# WX0_010_828DL.net
KiCad netlist of a schematic drawn in Altium Designer
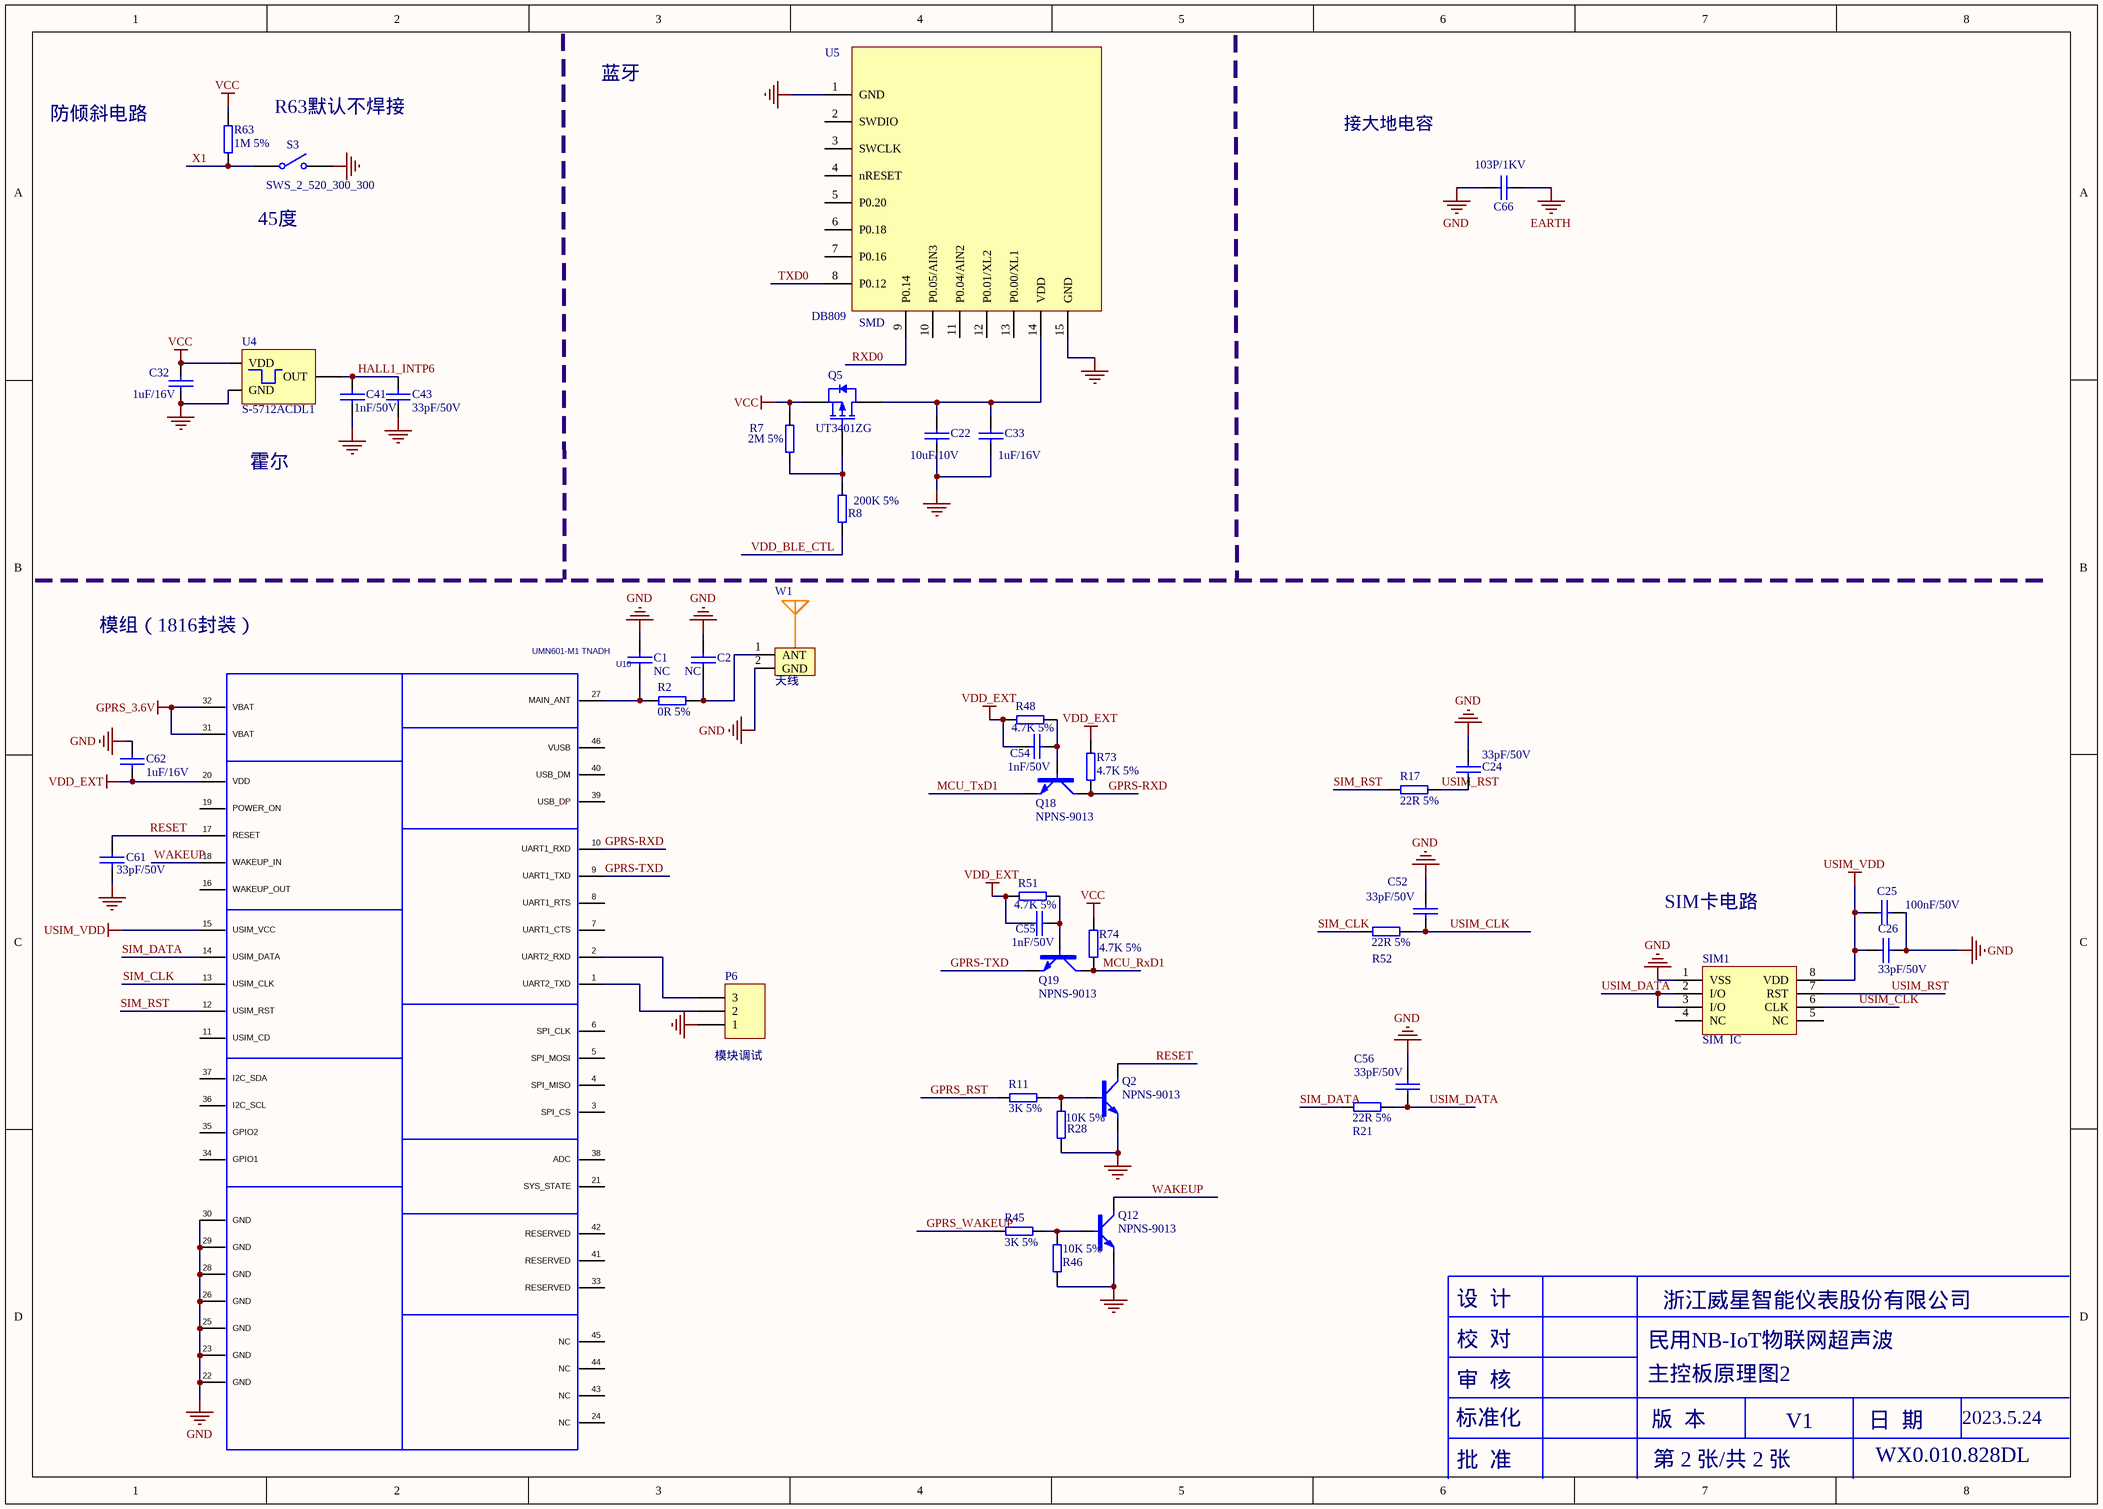
[diagram p0: WX0.010.828DL.SchDoc]

(export (version "E")
  (design (tool "Eeschema 10.0.6"))
  (components
    (comp (ref "C1")
      (value "NC")
      (footprint "CAP0603")
      (libsource (lib "Database_Libs2") (part "CC03JPO9_12P"))
    )
    (comp (ref "C2")
      (value "NC")
      (footprint "CAP0603")
      (libsource (lib "Database_Libs2") (part "CC03JPO9_12P"))
    )
    (comp (ref "C22")
      (value "10uF/10V")
      (footprint "CAP0603")
      (description "106pF,10 V,±10%,0603,村田,GRM188R61A106KE47D")
      (fields (field (name "PART NUMBER") "101020103-0026"))
      (libsource (lib "Database_Libs2") (part "CC03K5R6_10U"))
    )
    (comp (ref "C24")
      (value "33pF/50V")
      (footprint "CAP0603")
      (description "33pF,50 V,±10%,0603,国巨,CC0603KRNPO9BN33")
      (fields (field (name "PART NUMBER") "101020103-0027"))
      (libsource (lib "Database_Libs2") (part "CC03KPO9_33P"))
    )
    (comp (ref "C25")
      (value "100nF/50V")
      (footprint "CAP0603")
      (description "104pF,50 V,±10%,0603,国巨,CC0603KRX7R9BB104")
      (fields (field (name "PART NUMBER") "101020103-0021"))
      (libsource (lib "Database_Libs2") (part "CC03K7R9_100N"))
    )
    (comp (ref "C26")
      (value "33pF/50V")
      (footprint "CAP0603")
      (description "33pF,50 V,±10%,0603,国巨,CC0603KRNPO9BN33")
      (fields (field (name "PART NUMBER") "101020103-0027"))
      (libsource (lib "Database_Libs2") (part "CC03KPO9_33P"))
    )
    (comp (ref "C32")
      (value "1uF/16V")
      (footprint "CAP0603")
      (description "105pF,16 V,±10%,0603,国巨,CC0603KRX7R7BB105")
      (fields (field (name "PART NUMBER") "101020103-0003"))
      (libsource (lib "Database_Libs2") (part "CC03K7R7_1U"))
    )
    (comp (ref "C33")
      (value "1uF/16V")
      (footprint "CAP0603")
      (description "105pF,16 V,±10%,0603,国巨,CC0603KRX7R7BB105")
      (fields (field (name "PART NUMBER") "101020103-0003"))
      (libsource (lib "Database_Libs2") (part "CC03K7R7_1U"))
    )
    (comp (ref "C41")
      (value "1nF/50V")
      (footprint "CAP0603")
      (description "102pF,50 V,±10%,0603,国巨,CC0603KRX7R9BB102")
      (fields (field (name "PART NUMBER") "101020103-0022"))
      (libsource (lib "Database_Libs2") (part "CC03K7R9_1N"))
    )
    (comp (ref "C43")
      (value "33pF/50V")
      (footprint "CAP0603")
      (description "33pF,50 V,±10%,0603,国巨,CC0603KRNPO9BN33")
      (fields (field (name "PART NUMBER") "101020103-0027"))
      (libsource (lib "Database_Libs2") (part "CC03KPO9_33P"))
    )
    (comp (ref "C52")
      (value "33pF/50V")
      (footprint "CAP0603")
      (description "33pF,50 V,±10%,0603,国巨,CC0603KRNPO9BN33")
      (fields (field (name "PART NUMBER") "101020103-0027"))
      (libsource (lib "Database_Libs2") (part "CC03KPO9_33P"))
    )
    (comp (ref "C54")
      (value "1nF/50V")
      (footprint "CAP0603")
      (description "102pF,50 V,±10%,0603,国巨,CC0603KRX7R9BB102")
      (fields (field (name "PART NUMBER") "101020103-0022"))
      (libsource (lib "Database_Libs1") (part "CC03K7R9_1N"))
    )
    (comp (ref "C55")
      (value "1nF/50V")
      (footprint "CAP0603")
      (description "102pF,50 V,±10%,0603,国巨,CC0603KRX7R9BB102")
      (fields (field (name "PART NUMBER") "101020103-0022"))
      (libsource (lib "Database_Libs1") (part "CC03K7R9_1N"))
    )
    (comp (ref "C56")
      (value "33pF/50V")
      (footprint "CAP0603")
      (description "33pF,50 V,±10%,0603,国巨,CC0603KRNPO9BN33")
      (fields (field (name "PART NUMBER") "101020103-0027"))
      (libsource (lib "Database_Libs2") (part "CC03KPO9_33P"))
    )
    (comp (ref "C61")
      (value "33pF/50V")
      (footprint "CAP0603")
      (description "33pF,50 V,±10%,0603,国巨,CC0603KRNPO9BN33")
      (fields (field (name "PART NUMBER") "101020103-0027"))
      (libsource (lib "Database_Libs2") (part "CC03KPO9_33P"))
    )
    (comp (ref "C62")
      (value "1uF/16V")
      (footprint "CAP0603")
      (description "105pF,16 V,±10%,0603,国巨,CC0603KRX7R7BB105")
      (fields (field (name "PART NUMBER") "101020103-0003"))
      (libsource (lib "Database_Libs1") (part "CC03K7R7_1U"))
    )
    (comp (ref "C66")
      (value "103P/1KV")
      (footprint "CAP1206")
      (description "103P/1KV,±10％,1206")
      (fields (field (name "PART NUMBER") "101020101-0003"))
      (libsource (lib "altium-import") (part "root_3_CC03K7R9_100N_"))
    )
    (comp (ref "P6")
      (value "模块调试")
      (footprint "PIN254_1*3*WXHJ")
      (description "1*3 ，Φ1.0 ，2.54mm，直脚,无需焊接器件")
      (fields (field (name "PART NUMBER") "AD_WXHJ_PinHeader_04"))
      (libsource (lib "Database_Libs2") (part "PIN254_1*3*WXHJ"))
    )
    (comp (ref "Q2")
      (value "NPNS-9013")
      (footprint "SOT-23")
      (description "9013,NPN,SOT-23,长电,S9013")
      (fields (field (name "PART NUMBER") "101040201-0002"))
      (libsource (lib "Database_Libs2") (part "03_NPNS-9013"))
    )
    (comp (ref "Q5")
      (value "UT3401ZG")
      (footprint "SOT-23")
      (description "UT3401ZG,P-MOS,SOT-23,UTC,UT3401ZG")
      (fields (field (name "PART NUMBER") "101040201-0013"))
      (libsource (lib "Database_Libs2") (part "03_P-UT3401ZG"))
    )
    (comp (ref "Q12")
      (value "NPNS-9013")
      (footprint "SOT-23")
      (description "9013,NPN,SOT-23,长电,S9013")
      (fields (field (name "PART NUMBER") "101040201-0002"))
      (libsource (lib "Database_Libs2") (part "03_NPNS-9013"))
    )
    (comp (ref "Q18")
      (value "NPNS-9013")
      (footprint "SOT-23")
      (description "9013,NPN,SOT-23,长电,S9013")
      (fields (field (name "PART NUMBER") "101040201-0002"))
      (libsource (lib "Database_Libs1") (part "03_NPNS-9013"))
    )
    (comp (ref "Q19")
      (value "NPNS-9013")
      (footprint "SOT-23")
      (description "9013,NPN,SOT-23,长电,S9013")
      (fields (field (name "PART NUMBER") "101040201-0002"))
      (libsource (lib "Database_Libs1") (part "03_NPNS-9013"))
    )
    (comp (ref "R2")
      (value "0R 5%")
      (footprint "RES0603")
      (description "国巨,±5%,0603,,155 ℃,-55 ℃,RC0603J2-070RL,无铅,200 ppm/℃,1/10W,,0R")
      (fields (field (name "PART NUMBER") "101010103-0001"))
      (libsource (lib "Database_Libs2") (part "RC03J_0R"))
    )
    (comp (ref "R7")
      (value "2M 5%")
      (footprint "RES0603")
      (description "国巨,±5%,0603,,155 ℃,-55 ℃,RC0603JR-072ML,含铅,100 ppm/℃,1/10W,,2M")
      (fields (field (name "PART NUMBER") "101010103-0025"))
      (libsource (lib "Database_Libs2") (part "RC03J_2M"))
    )
    (comp (ref "R8")
      (value "200K 5%")
      (footprint "RES0603")
      (description "200K,±5%,1/10W,0603,国巨,RC0603JR-07200KL")
      (fields (field (name "PART NUMBER") "101010103-0034"))
      (libsource (lib "Database_Libs2") (part "RC03J_200K"))
    )
    (comp (ref "R11")
      (value "3K 5%")
      (footprint "RES0603")
      (description "国巨,±5%,0603,,155 ℃,-55 ℃,RC0603JR-073KL,无铅,100 ppm/℃,1/10W,,3K")
      (fields (field (name "PART NUMBER") "101010103-0006"))
      (libsource (lib "Database_Libs2") (part "RC03J_3K"))
    )
    (comp (ref "R17")
      (value "22R 5%")
      (footprint "RES0603")
      (description "国巨,±5%,0603,,155 ℃,-55 ℃,RC0603JR-0722RL,无铅,200 ppm/℃,1/10W,,22欧")
      (fields (field (name "PART NUMBER") "101010103-0009"))
      (libsource (lib "Database_Libs2") (part "RC03J_22R"))
    )
    (comp (ref "R21")
      (value "22R 5%")
      (footprint "RES0603")
      (description "国巨,±5%,0603,,155 ℃,-55 ℃,RC0603JR-0722RL,无铅,200 ppm/℃,1/10W,,22欧")
      (fields (field (name "PART NUMBER") "101010103-0009"))
      (libsource (lib "Database_Libs2") (part "RC03J_22R"))
    )
    (comp (ref "R28")
      (value "10K 5%")
      (footprint "RES0603")
      (description "国巨,±5%,0603,,155 ℃,-55 ℃,RC0603JR-0710KL,无铅,200 ppm/℃,1/10W,,10K")
      (fields (field (name "PART NUMBER") "101010103-0003"))
      (libsource (lib "Database_Libs2") (part "RC03J_10K"))
    )
    (comp (ref "R45")
      (value "3K 5%")
      (footprint "RES0603")
      (description "国巨,±5%,0603,,155 ℃,-55 ℃,RC0603JR-073KL,无铅,100 ppm/℃,1/10W,,3K")
      (fields (field (name "PART NUMBER") "101010103-0006"))
      (libsource (lib "Database_Libs2") (part "RC03J_3K"))
    )
    (comp (ref "R46")
      (value "10K 5%")
      (footprint "RES0603")
      (description "国巨,±5%,0603,,155 ℃,-55 ℃,RC0603JR-0710KL,无铅,200 ppm/℃,1/10W,,10K")
      (fields (field (name "PART NUMBER") "101010103-0003"))
      (libsource (lib "Database_Libs2") (part "RC03J_10K"))
    )
    (comp (ref "R48")
      (value "4.7K 5%")
      (footprint "RES0603")
      (description "4.7K±5%,1/10W,0603")
      (fields (field (name "PART NUMBER") "101010103-0042"))
      (libsource (lib "Database_Libs2") (part "RC03J_4.7K"))
    )
    (comp (ref "R51")
      (value "4.7K 5%")
      (footprint "RES0603")
      (description "4.7K±5%,1/10W,0603")
      (fields (field (name "PART NUMBER") "101010103-0042"))
      (libsource (lib "Database_Libs2") (part "RC03J_4.7K"))
    )
    (comp (ref "R52")
      (value "22R 5%")
      (footprint "RES0603")
      (description "国巨,±5%,0603,,155 ℃,-55 ℃,RC0603JR-0722RL,无铅,200 ppm/℃,1/10W,,22欧")
      (fields (field (name "PART NUMBER") "101010103-0009"))
      (libsource (lib "Database_Libs2") (part "RC03J_22R"))
    )
    (comp (ref "R63")
      (value "1M 5%")
      (footprint "RES0603")
      (description "国巨,±5%,0603,,155 ℃,-55 ℃,RC0603JR-071ML,无铅,200 ppm/℃,1/10W,,1M")
      (fields (field (name "PART NUMBER") "101010103-0002"))
      (libsource (lib "Database_Libs2") (part "RC03J_1M"))
    )
    (comp (ref "R73")
      (value "4.7K 5%")
      (footprint "RES0603")
      (description "4.7K±5%,1/10W,0603")
      (fields (field (name "PART NUMBER") "101010103-0042"))
      (libsource (lib "Database_Libs2") (part "RC03J_4.7K"))
    )
    (comp (ref "R74")
      (value "4.7K 5%")
      (footprint "RES0603")
      (description "4.7K±5%,1/10W,0603")
      (fields (field (name "PART NUMBER") "101010103-0042"))
      (libsource (lib "Database_Libs2") (part "RC03J_4.7K"))
    )
    (comp (ref "S3")
      (value "SWS_2_520_300_300")
      (footprint "SWS_2_520_300")
      (description "CSX-SEN-645B,垂直45°开关转换,3*5.2mm,360°任意方位倾斜检测,深圳市成晟科技有限公司")
      (fields (field (name "PART NUMBER") "1011001-0051"))
      (libsource (lib "Database_Libs2") (part "07_SWS_2_520_300_300"))
    )
    (comp (ref "SIM1")
      (value "SIM  IC")
      (footprint "SIMIC")
      (libsource (lib "PCB_Project") (part "SIMCARD_1"))
    )
    (comp (ref "U4")
      (value "S-5712ACDL1")
      (footprint "SOT-23")
      (description "S-5712ACDL1,SOT23-3,3.5 V,1.6 V,2 uA,精工电子,S-5712ACDL1")
      (fields (field (name "PART NUMBER") "1010504-0002"))
      (libsource (lib "Database_Libs2") (part "01_S-5712ACDL1"))
    )
    (comp (ref "U5")
      (value "DB809")
      (footprint "DB809")
      (description "北高智蓝牙模块DB809")
      (fields (field (name "PART NUMBER") "1011402-0194") (field (name "SMD/DIP") "SMD"))
      (libsource (lib "Database_Libs2") (part "01_DB809"))
    )
    (comp (ref "U10")
      (value "UMN601-M1 TNADH")
      (footprint "N700-FIXTURE_DL_CFT_CQA")
      (description "N700-58-01,N700-58-01,通信模块,18.0mm*16.0mm*2.1mm,Band 5:850MHz/Band 8:900MHz,深圳市广和通无线股份有限公司")
      (fields (field (name "PART NUMBER") "1011402-0183"))
      (libsource (lib "Database_Libs2") (part "01_N700_CON_46"))
    )
    (comp (ref "W1")
      (value "天线")
      (footprint "ANT-tanpian")
      (description "UB06000058A,3*3.1*1.25mm,公头,单排,IPEX一代板端")
      (fields (field (name "PART NUMBER") "1010902-0145"))
      (libsource (lib "Database_Libs2") (part "天线"))
    )
  )
  (nets
    (net (code "1") (name "/GPRS-RXD") (class "Default")
      (node (ref "Q18") (pin "3") (pinfunction "C_3") (pintype "passive"))
      (node (ref "R73") (pin "1") (pinfunction "1_1") (pintype "passive"))
      (node (ref "U10") (pin "10") (pinfunction "UART1_RXD_10") (pintype "passive"))
    )
    (net (code "2") (name "/GPRS-TXD") (class "Default")
      (node (ref "Q19") (pin "2") (pinfunction "E_2") (pintype "passive"))
      (node (ref "U10") (pin "9") (pinfunction "UART1_TXD_9") (pintype "passive"))
    )
    (net (code "3") (name "/GPRS_RST") (class "Default")
      (node (ref "R11") (pin "1") (pinfunction "1_1") (pintype "passive"))
    )
    (net (code "4") (name "/GPRS_WAKEUP") (class "Default")
      (node (ref "R45") (pin "1") (pinfunction "1_1") (pintype "passive"))
    )
    (net (code "5") (name "/HALL1_INTP6") (class "Default")
      (node (ref "C41") (pin "1") (pinfunction "1_1") (pintype "passive"))
      (node (ref "C43") (pin "1") (pinfunction "1_1") (pintype "passive"))
      (node (ref "U4") (pin "2") (pinfunction "OUT_2") (pintype "passive"))
    )
    (net (code "6") (name "/MCU_RxD1") (class "Default")
      (node (ref "Q19") (pin "3") (pinfunction "C_3") (pintype "passive"))
      (node (ref "R74") (pin "1") (pinfunction "1_1") (pintype "passive"))
    )
    (net (code "7") (name "/MCU_TxD1") (class "Default")
      (node (ref "Q18") (pin "2") (pinfunction "E_2") (pintype "passive"))
    )
    (net (code "8") (name "/RESET") (class "Default")
      (node (ref "C61") (pin "2") (pinfunction "2_2") (pintype "passive"))
      (node (ref "Q2") (pin "3") (pinfunction "C_3") (pintype "passive"))
      (node (ref "U10") (pin "17") (pinfunction "RESET_17") (pintype "passive"))
    )
    (net (code "9") (name "/RXD0") (class "Default")
      (node (ref "U5") (pin "9") (pinfunction "P0.14_9") (pintype "passive"))
    )
    (net (code "10") (name "/SIM_CLK") (class "Default")
      (node (ref "R52") (pin "1") (pinfunction "1_1") (pintype "passive"))
      (node (ref "U10") (pin "13") (pinfunction "USIM_CLK_13") (pintype "passive"))
    )
    (net (code "11") (name "/SIM_DATA") (class "Default")
      (node (ref "R21") (pin "1") (pinfunction "1_1") (pintype "passive"))
      (node (ref "U10") (pin "14") (pinfunction "USIM_DATA_14") (pintype "passive"))
    )
    (net (code "12") (name "/SIM_RST") (class "Default")
      (node (ref "R17") (pin "1") (pinfunction "1_1") (pintype "passive"))
      (node (ref "U10") (pin "12") (pinfunction "USIM_RST_12") (pintype "passive"))
    )
    (net (code "13") (name "/TXD0") (class "Default")
      (node (ref "U5") (pin "8") (pinfunction "P0.12_8") (pintype "passive"))
    )
    (net (code "14") (name "/USIM_CLK") (class "Default")
      (node (ref "C52") (pin "1") (pinfunction "1_1") (pintype "passive"))
      (node (ref "R52") (pin "2") (pinfunction "2_2") (pintype "passive"))
      (node (ref "SIM1") (pin "6") (pinfunction "CLK_6") (pintype "passive"))
    )
    (net (code "15") (name "/USIM_DATA") (class "Default")
      (node (ref "C56") (pin "1") (pinfunction "1_1") (pintype "passive"))
      (node (ref "R21") (pin "2") (pinfunction "2_2") (pintype "passive"))
      (node (ref "SIM1") (pin "2") (pinfunction "I/O_2") (pintype "passive"))
      (node (ref "SIM1") (pin "3") (pinfunction "I/O_3") (pintype "passive"))
    )
    (net (code "16") (name "/USIM_RST") (class "Default")
      (node (ref "C24") (pin "1") (pinfunction "1_1") (pintype "passive"))
      (node (ref "R17") (pin "2") (pinfunction "2_2") (pintype "passive"))
      (node (ref "SIM1") (pin "7") (pinfunction "RST_7") (pintype "passive"))
    )
    (net (code "17") (name "/VDD_BLE_CTL") (class "Default")
      (node (ref "R8") (pin "1") (pinfunction "1_1") (pintype "passive"))
    )
    (net (code "18") (name "/WAKEUP") (class "Default")
      (node (ref "Q12") (pin "3") (pinfunction "C_3") (pintype "passive"))
      (node (ref "U10") (pin "18") (pinfunction "WAKEUP_IN_18") (pintype "passive"))
    )
    (net (code "19") (name "/X1") (class "Default")
      (node (ref "R63") (pin "1") (pinfunction "1_1") (pintype "passive"))
      (node (ref "S3") (pin "1") (pintype "passive"))
    )
    (net (code "20") (name "EARTH") (class "Default")
      (node (ref "C66") (pin "1") (pinfunction "1_1") (pintype "passive"))
    )
    (net (code "21") (name "GND") (class "Default")
      (node (ref "C1") (pin "2") (pinfunction "2_2") (pintype "passive"))
      (node (ref "C2") (pin "2") (pinfunction "2_2") (pintype "passive"))
      (node (ref "C22") (pin "2") (pinfunction "2_2") (pintype "passive"))
      (node (ref "C24") (pin "2") (pinfunction "2_2") (pintype "passive"))
      (node (ref "C25") (pin "1") (pinfunction "1_1") (pintype "passive"))
      (node (ref "C26") (pin "2") (pinfunction "2_2") (pintype "passive"))
      (node (ref "C32") (pin "2") (pinfunction "2_2") (pintype "passive"))
      (node (ref "C33") (pin "2") (pinfunction "2_2") (pintype "passive"))
      (node (ref "C41") (pin "2") (pinfunction "2_2") (pintype "passive"))
      (node (ref "C43") (pin "2") (pinfunction "2_2") (pintype "passive"))
      (node (ref "C52") (pin "2") (pinfunction "2_2") (pintype "passive"))
      (node (ref "C56") (pin "2") (pinfunction "2_2") (pintype "passive"))
      (node (ref "C61") (pin "1") (pinfunction "1_1") (pintype "passive"))
      (node (ref "C62") (pin "2") (pinfunction "2_2") (pintype "passive"))
      (node (ref "C66") (pin "2") (pinfunction "2_2") (pintype "passive"))
      (node (ref "P6") (pin "1") (pinfunction "1_1") (pintype "passive"))
      (node (ref "Q12") (pin "2") (pinfunction "E_2") (pintype "passive"))
      (node (ref "Q2") (pin "2") (pinfunction "E_2") (pintype "passive"))
      (node (ref "R28") (pin "1") (pinfunction "1_1") (pintype "passive"))
      (node (ref "R46") (pin "1") (pinfunction "1_1") (pintype "passive"))
      (node (ref "S3") (pin "2") (pintype "passive"))
      (node (ref "SIM1") (pin "1") (pinfunction "VSS_1") (pintype "passive"))
      (node (ref "U10") (pin "22") (pinfunction "GND_22") (pintype "passive"))
      (node (ref "U10") (pin "23") (pinfunction "GND_23") (pintype "passive"))
      (node (ref "U10") (pin "25") (pinfunction "GND_25") (pintype "passive"))
      (node (ref "U10") (pin "26") (pinfunction "GND_26") (pintype "passive"))
      (node (ref "U10") (pin "28") (pinfunction "GND_28") (pintype "passive"))
      (node (ref "U10") (pin "29") (pinfunction "GND_29") (pintype "passive"))
      (node (ref "U10") (pin "30") (pinfunction "GND_30") (pintype "passive"))
      (node (ref "U4") (pin "3") (pinfunction "GND_3") (pintype "passive"))
      (node (ref "U5") (pin "1") (pinfunction "GND_1") (pintype "passive"))
      (node (ref "U5") (pin "15") (pinfunction "GND_15") (pintype "passive"))
      (node (ref "W1") (pin "2") (pinfunction "GND_2") (pintype "passive"))
    )
    (net (code "22") (name "GPRS_3.6V") (class "Default")
      (node (ref "U10") (pin "31") (pinfunction "VBAT_31") (pintype "passive"))
      (node (ref "U10") (pin "32") (pinfunction "VBAT_32") (pintype "passive"))
    )
    (net (code "23") (name "Net-(Q2-B)") (class "Default")
      (node (ref "Q2") (pin "1") (pinfunction "B_1") (pintype "passive"))
      (node (ref "R11") (pin "2") (pinfunction "2_2") (pintype "passive"))
      (node (ref "R28") (pin "2") (pinfunction "2_2") (pintype "passive"))
    )
    (net (code "24") (name "Net-(Q5-D)") (class "Default")
      (node (ref "C22") (pin "1") (pinfunction "1_1") (pintype "passive"))
      (node (ref "C33") (pin "1") (pinfunction "1_1") (pintype "passive"))
      (node (ref "Q5") (pin "3") (pinfunction "D_3") (pintype "passive"))
      (node (ref "U5") (pin "14") (pinfunction "VDD_14") (pintype "passive"))
    )
    (net (code "25") (name "Net-(Q5-G)") (class "Default")
      (node (ref "Q5") (pin "1") (pinfunction "G_1") (pintype "passive"))
      (node (ref "R7") (pin "1") (pinfunction "1_1") (pintype "passive"))
      (node (ref "R8") (pin "2") (pinfunction "2_2") (pintype "passive"))
    )
    (net (code "26") (name "Net-(Q12-B)") (class "Default")
      (node (ref "Q12") (pin "1") (pinfunction "B_1") (pintype "passive"))
      (node (ref "R45") (pin "2") (pinfunction "2_2") (pintype "passive"))
      (node (ref "R46") (pin "2") (pinfunction "2_2") (pintype "passive"))
    )
    (net (code "27") (name "Net-(Q18-B)") (class "Default")
      (node (ref "C54") (pin "2") (pinfunction "2_2") (pintype "passive"))
      (node (ref "Q18") (pin "1") (pinfunction "B_1") (pintype "passive"))
      (node (ref "R48") (pin "1") (pinfunction "1_1") (pintype "passive"))
    )
    (net (code "28") (name "Net-(Q19-B)") (class "Default")
      (node (ref "C55") (pin "2") (pinfunction "2_2") (pintype "passive"))
      (node (ref "Q19") (pin "1") (pinfunction "B_1") (pintype "passive"))
      (node (ref "R51") (pin "1") (pinfunction "1_1") (pintype "passive"))
    )
    (net (code "29") (name "Net-(U10-MAIN_ANT)") (class "Default")
      (node (ref "C1") (pin "1") (pinfunction "1_1") (pintype "passive"))
      (node (ref "R2") (pin "2") (pinfunction "2_2") (pintype "passive"))
      (node (ref "U10") (pin "27") (pinfunction "MAIN_ANT_27") (pintype "passive"))
    )
    (net (code "30") (name "Net-(U10-UART2_RXD)") (class "Default")
      (node (ref "P6") (pin "3") (pinfunction "3_3") (pintype "passive"))
      (node (ref "U10") (pin "2") (pinfunction "UART2_RXD_2") (pintype "passive"))
    )
    (net (code "31") (name "Net-(U10-UART2_TXD)") (class "Default")
      (node (ref "P6") (pin "2") (pinfunction "2_2") (pintype "passive"))
      (node (ref "U10") (pin "1") (pinfunction "UART2_TXD_1") (pintype "passive"))
    )
    (net (code "32") (name "Net-(W1-ANT)") (class "Default")
      (node (ref "C2") (pin "1") (pinfunction "1_1") (pintype "passive"))
      (node (ref "R2") (pin "1") (pinfunction "1_1") (pintype "passive"))
      (node (ref "W1") (pin "1") (pinfunction "ANT_1") (pintype "passive"))
    )
    (net (code "33") (name "USIM_VDD") (class "Default")
      (node (ref "C25") (pin "2") (pinfunction "2_2") (pintype "passive"))
      (node (ref "C26") (pin "1") (pinfunction "1_1") (pintype "passive"))
      (node (ref "SIM1") (pin "8") (pinfunction "VDD_8") (pintype "passive"))
      (node (ref "U10") (pin "15") (pinfunction "USIM_VCC_15") (pintype "passive"))
    )
    (net (code "34") (name "VCC") (class "Default")
      (node (ref "C32") (pin "1") (pinfunction "1_1") (pintype "passive"))
      (node (ref "Q5") (pin "2") (pinfunction "S_2") (pintype "passive"))
      (node (ref "R63") (pin "2") (pinfunction "2_2") (pintype "passive"))
      (node (ref "R7") (pin "2") (pinfunction "2_2") (pintype "passive"))
      (node (ref "R74") (pin "2") (pinfunction "2_2") (pintype "passive"))
      (node (ref "U4") (pin "1") (pinfunction "VDD_1") (pintype "passive"))
    )
    (net (code "35") (name "VDD_EXT") (class "Default")
      (node (ref "C54") (pin "1") (pinfunction "1_1") (pintype "passive"))
      (node (ref "C55") (pin "1") (pinfunction "1_1") (pintype "passive"))
      (node (ref "C62") (pin "1") (pinfunction "1_1") (pintype "passive"))
      (node (ref "R48") (pin "2") (pinfunction "2_2") (pintype "passive"))
      (node (ref "R51") (pin "2") (pinfunction "2_2") (pintype "passive"))
      (node (ref "R73") (pin "2") (pinfunction "2_2") (pintype "passive"))
      (node (ref "U10") (pin "20") (pinfunction "VDD_20") (pintype "passive"))
    )
    (net (code "36") (name "unconnected-(SIM1-NC-Pad4)") (class "Default")
      (node (ref "SIM1") (pin "4") (pinfunction "NC_4") (pintype "passive"))
    )
    (net (code "37") (name "unconnected-(SIM1-NC-Pad5)") (class "Default")
      (node (ref "SIM1") (pin "5") (pinfunction "NC_5") (pintype "passive"))
    )
    (net (code "38") (name "unconnected-(U5-P0.00{slash}XL1-Pad13)") (class "Default")
      (node (ref "U5") (pin "13") (pinfunction "P0.00/XL1_13") (pintype "passive"))
    )
    (net (code "39") (name "unconnected-(U5-P0.01{slash}XL2-Pad12)") (class "Default")
      (node (ref "U5") (pin "12") (pinfunction "P0.01/XL2_12") (pintype "passive"))
    )
    (net (code "40") (name "unconnected-(U5-P0.04{slash}AIN2-Pad11)") (class "Default")
      (node (ref "U5") (pin "11") (pinfunction "P0.04/AIN2_11") (pintype "passive"))
    )
    (net (code "41") (name "unconnected-(U5-P0.05{slash}AIN3-Pad10)") (class "Default")
      (node (ref "U5") (pin "10") (pinfunction "P0.05/AIN3_10") (pintype "passive"))
    )
    (net (code "42") (name "unconnected-(U5-P0.16-Pad7)") (class "Default")
      (node (ref "U5") (pin "7") (pinfunction "P0.16_7") (pintype "passive"))
    )
    (net (code "43") (name "unconnected-(U5-P0.18-Pad6)") (class "Default")
      (node (ref "U5") (pin "6") (pinfunction "P0.18_6") (pintype "passive"))
    )
    (net (code "44") (name "unconnected-(U5-P0.20-Pad5)") (class "Default")
      (node (ref "U5") (pin "5") (pinfunction "P0.20_5") (pintype "passive"))
    )
    (net (code "45") (name "unconnected-(U5-SWCLK-Pad3)") (class "Default")
      (node (ref "U5") (pin "3") (pinfunction "SWCLK_3") (pintype "passive"))
    )
    (net (code "46") (name "unconnected-(U5-SWDIO-Pad2)") (class "Default")
      (node (ref "U5") (pin "2") (pinfunction "SWDIO_2") (pintype "passive"))
    )
    (net (code "47") (name "unconnected-(U5-nRESET-Pad4)") (class "Default")
      (node (ref "U5") (pin "4") (pinfunction "nRESET_4") (pintype "passive"))
    )
    (net (code "48") (name "unconnected-(U10-ADC-Pad38)") (class "Default")
      (node (ref "U10") (pin "38") (pinfunction "ADC_38") (pintype "passive"))
    )
    (net (code "49") (name "unconnected-(U10-GPIO1-Pad34)") (class "Default")
      (node (ref "U10") (pin "34") (pinfunction "GPIO1_34") (pintype "passive"))
    )
    (net (code "50") (name "unconnected-(U10-GPIO2-Pad35)") (class "Default")
      (node (ref "U10") (pin "35") (pinfunction "GPIO2_35") (pintype "passive"))
    )
    (net (code "51") (name "unconnected-(U10-I2C_SCL-Pad36)") (class "Default")
      (node (ref "U10") (pin "36") (pinfunction "I2C_SCL_36") (pintype "passive"))
    )
    (net (code "52") (name "unconnected-(U10-I2C_SDA-Pad37)") (class "Default")
      (node (ref "U10") (pin "37") (pinfunction "I2C_SDA_37") (pintype "passive"))
    )
    (net (code "53") (name "unconnected-(U10-NC-Pad24)") (class "Default")
      (node (ref "U10") (pin "24") (pinfunction "NC_24") (pintype "passive"))
    )
    (net (code "54") (name "unconnected-(U10-NC-Pad43)") (class "Default")
      (node (ref "U10") (pin "43") (pinfunction "NC_43") (pintype "passive"))
    )
    (net (code "55") (name "unconnected-(U10-NC-Pad44)") (class "Default")
      (node (ref "U10") (pin "44") (pinfunction "NC_44") (pintype "passive"))
    )
    (net (code "56") (name "unconnected-(U10-NC-Pad45)") (class "Default")
      (node (ref "U10") (pin "45") (pinfunction "NC_45") (pintype "passive"))
    )
    (net (code "57") (name "unconnected-(U10-POWER_ON-Pad19)") (class "Default")
      (node (ref "U10") (pin "19") (pinfunction "POWER_ON_19") (pintype "passive"))
    )
    (net (code "58") (name "unconnected-(U10-RESERVED-Pad33)") (class "Default")
      (node (ref "U10") (pin "33") (pinfunction "RESERVED_33") (pintype "passive"))
    )
    (net (code "59") (name "unconnected-(U10-RESERVED-Pad41)") (class "Default")
      (node (ref "U10") (pin "41") (pinfunction "RESERVED_41") (pintype "passive"))
    )
    (net (code "60") (name "unconnected-(U10-RESERVED-Pad42)") (class "Default")
      (node (ref "U10") (pin "42") (pinfunction "RESERVED_42") (pintype "passive"))
    )
    (net (code "61") (name "unconnected-(U10-SPI_CLK-Pad6)") (class "Default")
      (node (ref "U10") (pin "6") (pinfunction "SPI_CLK_6") (pintype "passive"))
    )
    (net (code "62") (name "unconnected-(U10-SPI_CS-Pad3)") (class "Default")
      (node (ref "U10") (pin "3") (pinfunction "SPI_CS_3") (pintype "passive"))
    )
    (net (code "63") (name "unconnected-(U10-SPI_MISO-Pad4)") (class "Default")
      (node (ref "U10") (pin "4") (pinfunction "SPI_MISO_4") (pintype "passive"))
    )
    (net (code "64") (name "unconnected-(U10-SPI_MOSI-Pad5)") (class "Default")
      (node (ref "U10") (pin "5") (pinfunction "SPI_MOSI_5") (pintype "passive"))
    )
    (net (code "65") (name "unconnected-(U10-SYS_STATE-Pad21)") (class "Default")
      (node (ref "U10") (pin "21") (pinfunction "SYS_STATE_21") (pintype "passive"))
    )
    (net (code "66") (name "unconnected-(U10-UART1_CTS-Pad7)") (class "Default")
      (node (ref "U10") (pin "7") (pinfunction "UART1_CTS_7") (pintype "passive"))
    )
    (net (code "67") (name "unconnected-(U10-UART1_RTS-Pad8)") (class "Default")
      (node (ref "U10") (pin "8") (pinfunction "UART1_RTS_8") (pintype "passive"))
    )
    (net (code "68") (name "unconnected-(U10-USB_DM-Pad40)") (class "Default")
      (node (ref "U10") (pin "40") (pinfunction "USB_DM_40") (pintype "passive"))
    )
    (net (code "69") (name "unconnected-(U10-USB_DP-Pad39)") (class "Default")
      (node (ref "U10") (pin "39") (pinfunction "USB_DP_39") (pintype "passive"))
    )
    (net (code "70") (name "unconnected-(U10-USIM_CD-Pad11)") (class "Default")
      (node (ref "U10") (pin "11") (pinfunction "USIM_CD_11") (pintype "passive"))
    )
    (net (code "71") (name "unconnected-(U10-VUSB-Pad46)") (class "Default")
      (node (ref "U10") (pin "46") (pinfunction "VUSB_46") (pintype "passive"))
    )
    (net (code "72") (name "unconnected-(U10-WAKEUP_OUT-Pad16)") (class "Default")
      (node (ref "U10") (pin "16") (pinfunction "WAKEUP_OUT_16") (pintype "passive"))
    )
  )
)
